# Serial_Board.net
KiCad netlist of a schematic drawn in EAGLE
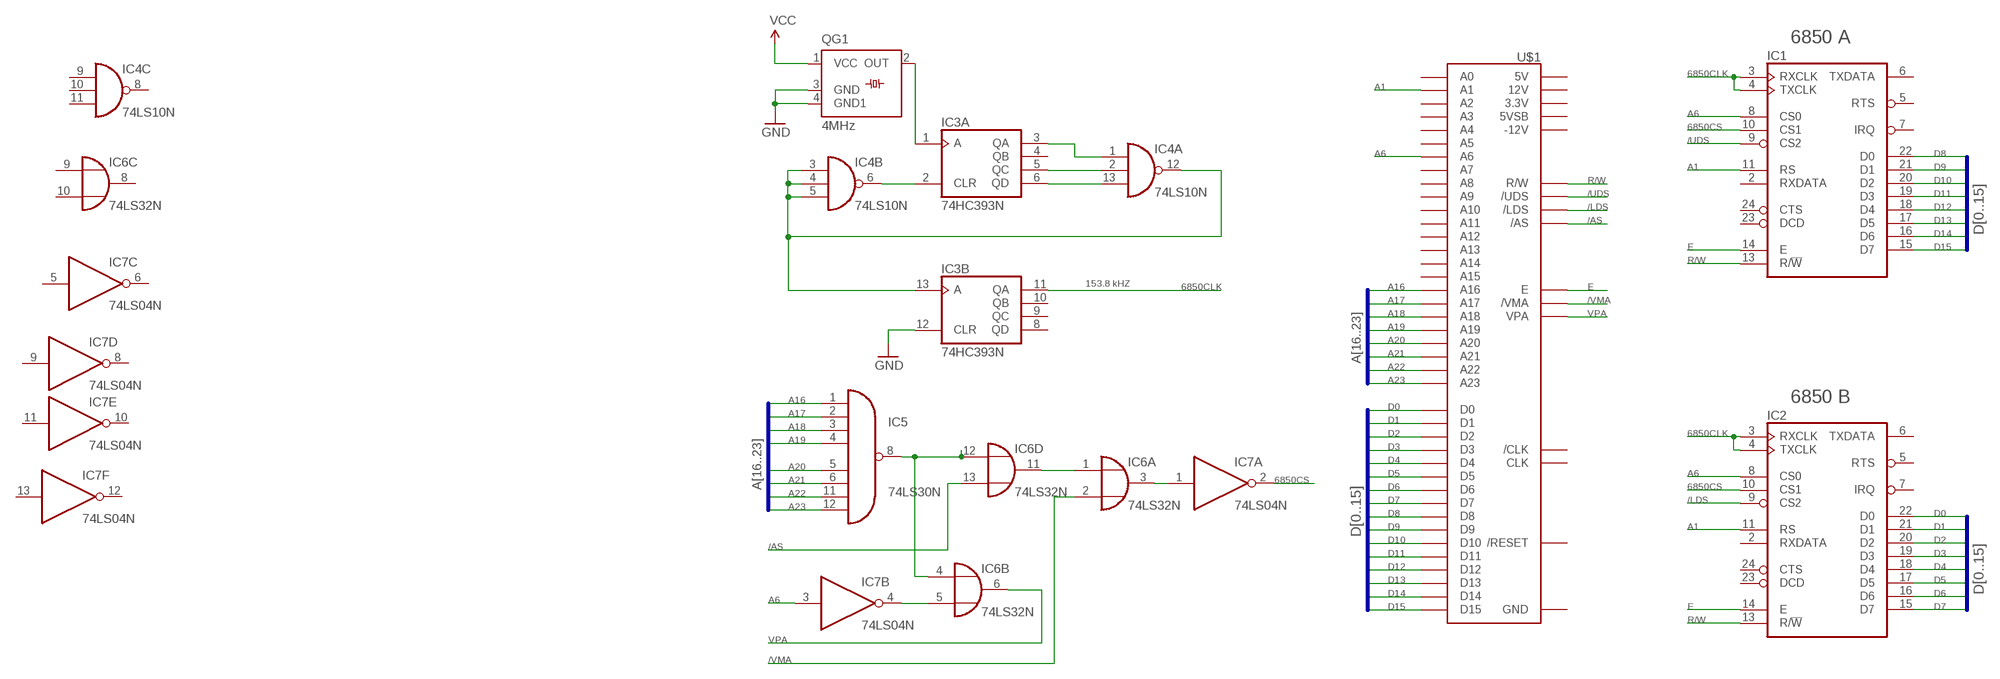
[diagram p0: schematic, sheet 1]

(export (version "E")
  (design (tool "Eeschema 10.0.6"))
  (components
    (comp (ref "IC1")
      (value "6850")
      (footprint "eagle-import:DIL24")
      (fields (field (name "MF") "NTE ELECTRONICS") (field (name "MPN") "NTE6850"))
      (libsource (lib "eagle-import") (part "6850"))
    )
    (comp (ref "IC2")
      (value "6850")
      (footprint "eagle-import:DIL24")
      (fields (field (name "MF") "NTE ELECTRONICS") (field (name "MPN") "NTE6850"))
      (libsource (lib "eagle-import") (part "6850"))
    )
    (comp (ref "IC3")
      (value "74HC393N")
      (footprint "eagle-import:DIL14")
      (libsource (lib "eagle-import") (part "74393NHC"))
    )
    (comp (ref "IC4")
      (value "74LS10N")
      (footprint "eagle-import:DIL14")
      (libsource (lib "eagle-import") (part "7410NLS"))
    )
    (comp (ref "IC5")
      (value "74LS30N")
      (footprint "eagle-import:DIL14")
      (libsource (lib "eagle-import") (part "7430NLS"))
    )
    (comp (ref "IC6")
      (value "74LS32N")
      (footprint "eagle-import:DIL14")
      (libsource (lib "eagle-import") (part "7432NLS"))
    )
    (comp (ref "IC7")
      (value "74LS04N")
      (footprint "eagle-import:DIL14")
      (libsource (lib "eagle-import") (part "7404NLS"))
    )
    (comp (ref "QG1")
      (value "4MHz")
      (footprint "eagle-import:TC49")
      (libsource (lib "eagle-import") (part "TC49C"))
    )
    (comp (ref "U$1")
      (value "BLANKBOARD")
      (footprint "eagle-import:BLANKBOARD")
      (libsource (lib "eagle-import") (part "BLANKBOARD"))
    )
  )
  (nets
    (net (code "1") (name "/6850CLK") (class "Default")
      (node (ref "IC1") (pin "3") (pinfunction "RXCLK_3") (pintype "input"))
      (node (ref "IC1") (pin "4") (pinfunction "TXCLK_4") (pintype "input"))
      (node (ref "IC2") (pin "3") (pinfunction "RXCLK_3") (pintype "input"))
      (node (ref "IC2") (pin "4") (pinfunction "TXCLK_4") (pintype "input"))
      (node (ref "IC3") (pin "11") (pinfunction "QA_11") (pintype "output"))
    )
    (net (code "2") (name "/6850CS") (class "Default")
      (node (ref "IC1") (pin "10") (pinfunction "CS1_10") (pintype "input"))
      (node (ref "IC2") (pin "10") (pinfunction "CS1_10") (pintype "input"))
      (node (ref "IC7") (pin "2") (pinfunction "O_2") (pintype "output"))
    )
    (net (code "3") (name "/A1") (class "Default")
      (node (ref "IC1") (pin "11") (pinfunction "RS_11") (pintype "input"))
      (node (ref "IC2") (pin "11") (pinfunction "RS_11") (pintype "input"))
      (node (ref "U$1") (pin "A1") (pinfunction "A1_A1") (pintype "bidirectional"))
    )
    (net (code "4") (name "/A6") (class "Default")
      (node (ref "IC1") (pin "8") (pinfunction "CS0_8") (pintype "input"))
      (node (ref "IC2") (pin "8") (pinfunction "CS0_8") (pintype "input"))
      (node (ref "IC7") (pin "3") (pinfunction "I_3") (pintype "input"))
      (node (ref "U$1") (pin "A6") (pinfunction "A6_A6") (pintype "bidirectional"))
    )
    (net (code "5") (name "/A16") (class "Default")
      (node (ref "IC5") (pin "1") (pinfunction "I0_1") (pintype "input"))
      (node (ref "U$1") (pin "A16") (pinfunction "A16_A16") (pintype "bidirectional"))
    )
    (net (code "6") (name "/A17") (class "Default")
      (node (ref "IC5") (pin "2") (pinfunction "I1_2") (pintype "input"))
      (node (ref "U$1") (pin "A17") (pinfunction "A17_A17") (pintype "bidirectional"))
    )
    (net (code "7") (name "/A18") (class "Default")
      (node (ref "IC5") (pin "3") (pinfunction "I2_3") (pintype "input"))
      (node (ref "U$1") (pin "A18") (pinfunction "A18_A18") (pintype "bidirectional"))
    )
    (net (code "8") (name "/A19") (class "Default")
      (node (ref "IC5") (pin "4") (pinfunction "I3_4") (pintype "input"))
      (node (ref "U$1") (pin "A19") (pinfunction "A19_A19") (pintype "bidirectional"))
    )
    (net (code "9") (name "/A20") (class "Default")
      (node (ref "IC5") (pin "5") (pinfunction "I4_5") (pintype "input"))
      (node (ref "U$1") (pin "A20") (pinfunction "A20_A20") (pintype "bidirectional"))
    )
    (net (code "10") (name "/A21") (class "Default")
      (node (ref "IC5") (pin "6") (pinfunction "I5_6") (pintype "input"))
      (node (ref "U$1") (pin "A21") (pinfunction "A21_A21") (pintype "bidirectional"))
    )
    (net (code "11") (name "/A22") (class "Default")
      (node (ref "IC5") (pin "11") (pinfunction "I6_11") (pintype "input"))
      (node (ref "U$1") (pin "A22") (pinfunction "A22_A22") (pintype "bidirectional"))
    )
    (net (code "12") (name "/A23") (class "Default")
      (node (ref "IC5") (pin "12") (pinfunction "I7_12") (pintype "input"))
      (node (ref "U$1") (pin "A23") (pinfunction "A23_A23") (pintype "bidirectional"))
    )
    (net (code "14") (name "/D0") (class "Default")
      (node (ref "IC2") (pin "22") (pinfunction "D0_22") (pintype "bidirectional"))
      (node (ref "U$1") (pin "D0") (pinfunction "D0_D0") (pintype "bidirectional"))
    )
    (net (code "15") (name "/D1") (class "Default")
      (node (ref "IC2") (pin "21") (pinfunction "D1_21") (pintype "bidirectional"))
      (node (ref "U$1") (pin "D1") (pinfunction "D1_D1") (pintype "bidirectional"))
    )
    (net (code "16") (name "/D2") (class "Default")
      (node (ref "IC2") (pin "20") (pinfunction "D2_20") (pintype "bidirectional"))
      (node (ref "U$1") (pin "D2") (pinfunction "D2_D2") (pintype "bidirectional"))
    )
    (net (code "17") (name "/D3") (class "Default")
      (node (ref "IC2") (pin "19") (pinfunction "D3_19") (pintype "bidirectional"))
      (node (ref "U$1") (pin "D3") (pinfunction "D3_D3") (pintype "bidirectional"))
    )
    (net (code "18") (name "/D4") (class "Default")
      (node (ref "IC2") (pin "18") (pinfunction "D4_18") (pintype "bidirectional"))
      (node (ref "U$1") (pin "D4") (pinfunction "D4_D4") (pintype "bidirectional"))
    )
    (net (code "19") (name "/D5") (class "Default")
      (node (ref "IC2") (pin "17") (pinfunction "D5_17") (pintype "bidirectional"))
      (node (ref "U$1") (pin "D5") (pinfunction "D5_D5") (pintype "bidirectional"))
    )
    (net (code "20") (name "/D6") (class "Default")
      (node (ref "IC2") (pin "16") (pinfunction "D6_16") (pintype "bidirectional"))
      (node (ref "U$1") (pin "D6") (pinfunction "D6_D6") (pintype "bidirectional"))
    )
    (net (code "21") (name "/D7") (class "Default")
      (node (ref "IC2") (pin "15") (pinfunction "D7_15") (pintype "bidirectional"))
      (node (ref "U$1") (pin "D7") (pinfunction "D7_D7") (pintype "bidirectional"))
    )
    (net (code "22") (name "/D8") (class "Default")
      (node (ref "IC1") (pin "22") (pinfunction "D0_22") (pintype "bidirectional"))
      (node (ref "U$1") (pin "D8") (pinfunction "D8_D8") (pintype "bidirectional"))
    )
    (net (code "23") (name "/D9") (class "Default")
      (node (ref "IC1") (pin "21") (pinfunction "D1_21") (pintype "bidirectional"))
      (node (ref "U$1") (pin "D9") (pinfunction "D9_D9") (pintype "bidirectional"))
    )
    (net (code "24") (name "/D10") (class "Default")
      (node (ref "IC1") (pin "20") (pinfunction "D2_20") (pintype "bidirectional"))
      (node (ref "U$1") (pin "D10") (pinfunction "D10_D10") (pintype "bidirectional"))
    )
    (net (code "25") (name "/D11") (class "Default")
      (node (ref "IC1") (pin "19") (pinfunction "D3_19") (pintype "bidirectional"))
      (node (ref "U$1") (pin "D11") (pinfunction "D11_D11") (pintype "bidirectional"))
    )
    (net (code "26") (name "/D12") (class "Default")
      (node (ref "IC1") (pin "18") (pinfunction "D4_18") (pintype "bidirectional"))
      (node (ref "U$1") (pin "D12") (pinfunction "D12_D12") (pintype "bidirectional"))
    )
    (net (code "27") (name "/D13") (class "Default")
      (node (ref "IC1") (pin "17") (pinfunction "D5_17") (pintype "bidirectional"))
      (node (ref "U$1") (pin "D13") (pinfunction "D13_D13") (pintype "bidirectional"))
    )
    (net (code "28") (name "/D14") (class "Default")
      (node (ref "IC1") (pin "16") (pinfunction "D6_16") (pintype "bidirectional"))
      (node (ref "U$1") (pin "D14") (pinfunction "D14_D14") (pintype "bidirectional"))
    )
    (net (code "29") (name "/D15") (class "Default")
      (node (ref "IC1") (pin "15") (pinfunction "D7_15") (pintype "bidirectional"))
      (node (ref "U$1") (pin "D15") (pinfunction "D15_D15") (pintype "bidirectional"))
    )
    (net (code "31") (name "/E") (class "Default")
      (node (ref "IC1") (pin "14") (pinfunction "E_14") (pintype "input"))
      (node (ref "IC2") (pin "14") (pinfunction "E_14") (pintype "input"))
      (node (ref "U$1") (pin "E") (pinfunction "E_E") (pintype "bidirectional"))
    )
    (net (code "32") (name "/R{slash}W") (class "Default")
      (node (ref "IC1") (pin "13") (pinfunction "R/~{W}_13") (pintype "input"))
      (node (ref "IC2") (pin "13") (pinfunction "R/~{W}_13") (pintype "input"))
      (node (ref "U$1") (pin "R/W") (pinfunction "R/W_R/W") (pintype "bidirectional"))
    )
    (net (code "33") (name "/VPA") (class "Default")
      (node (ref "IC6") (pin "6") (pinfunction "O_6") (pintype "output"))
      (node (ref "U$1") (pin "VPA") (pinfunction "VPA_VPA") (pintype "bidirectional"))
    )
    (net (code "34") (name "/{slash}AS") (class "Default")
      (node (ref "IC6") (pin "13") (pinfunction "I1_13") (pintype "input"))
      (node (ref "U$1") (pin "/AS") (pinfunction "/AS_/AS") (pintype "bidirectional"))
    )
    (net (code "35") (name "/{slash}LDS") (class "Default")
      (node (ref "IC2") (pin "9") (pinfunction "CS2_9") (pintype "input"))
      (node (ref "U$1") (pin "/LDS") (pinfunction "/LDS_/LDS") (pintype "bidirectional"))
    )
    (net (code "36") (name "/{slash}UDS") (class "Default")
      (node (ref "IC1") (pin "9") (pinfunction "CS2_9") (pintype "input"))
      (node (ref "U$1") (pin "/UDS") (pinfunction "/UDS_/UDS") (pintype "bidirectional"))
    )
    (net (code "37") (name "/{slash}VMA") (class "Default")
      (node (ref "IC6") (pin "2") (pinfunction "I1_2") (pintype "input"))
      (node (ref "U$1") (pin "/VMA") (pinfunction "/VMA_/VMA") (pintype "bidirectional"))
    )
    (net (code "38") (name "GND") (class "Default")
      (node (ref "IC3") (pin "12") (pinfunction "CLR_12") (pintype "input"))
      (node (ref "QG1") (pin "3") (pinfunction "GND_3") (pintype "power_in"))
      (node (ref "QG1") (pin "4") (pinfunction "GND1_4") (pintype "power_in"))
    )
    (net (code "39") (name "Net-(IC3A-A)") (class "Default")
      (node (ref "IC3") (pin "1") (pinfunction "A_1") (pintype "input"))
      (node (ref "QG1") (pin "2") (pinfunction "OUT_2") (pintype "output"))
    )
    (net (code "40") (name "Net-(IC3A-CLR)") (class "Default")
      (node (ref "IC3") (pin "2") (pinfunction "CLR_2") (pintype "input"))
      (node (ref "IC4") (pin "6") (pinfunction "O_6") (pintype "output"))
    )
    (net (code "41") (name "Net-(IC3A-QA)") (class "Default")
      (node (ref "IC3") (pin "3") (pinfunction "QA_3") (pintype "output"))
      (node (ref "IC4") (pin "1") (pinfunction "I0_1") (pintype "input"))
    )
    (net (code "42") (name "Net-(IC3A-QC)") (class "Default")
      (node (ref "IC3") (pin "5") (pinfunction "QC_5") (pintype "output"))
      (node (ref "IC4") (pin "2") (pinfunction "I1_2") (pintype "input"))
    )
    (net (code "43") (name "Net-(IC3A-QD)") (class "Default")
      (node (ref "IC3") (pin "6") (pinfunction "QD_6") (pintype "output"))
      (node (ref "IC4") (pin "13") (pinfunction "I2_13") (pintype "input"))
    )
    (net (code "44") (name "Net-(IC3B-A)") (class "Default")
      (node (ref "IC3") (pin "13") (pinfunction "A_13") (pintype "input"))
      (node (ref "IC4") (pin "12") (pinfunction "O_12") (pintype "output"))
      (node (ref "IC4") (pin "3") (pinfunction "I0_3") (pintype "input"))
      (node (ref "IC4") (pin "4") (pinfunction "I1_4") (pintype "input"))
      (node (ref "IC4") (pin "5") (pinfunction "I2_5") (pintype "input"))
    )
    (net (code "45") (name "Net-(IC5A-O)") (class "Default")
      (node (ref "IC5") (pin "8") (pinfunction "O_8") (pintype "output"))
      (node (ref "IC6") (pin "12") (pinfunction "I0_12") (pintype "input"))
      (node (ref "IC6") (pin "4") (pinfunction "I0_4") (pintype "input"))
    )
    (net (code "46") (name "Net-(IC6A-I0)") (class "Default")
      (node (ref "IC6") (pin "1") (pinfunction "I0_1") (pintype "input"))
      (node (ref "IC6") (pin "11") (pinfunction "O_11") (pintype "output"))
    )
    (net (code "47") (name "Net-(IC6A-O)") (class "Default")
      (node (ref "IC6") (pin "3") (pinfunction "O_3") (pintype "output"))
      (node (ref "IC7") (pin "1") (pinfunction "I_1") (pintype "input"))
    )
    (net (code "48") (name "Net-(IC6B-I1)") (class "Default")
      (node (ref "IC6") (pin "5") (pinfunction "I1_5") (pintype "input"))
      (node (ref "IC7") (pin "4") (pinfunction "O_4") (pintype "output"))
    )
    (net (code "49") (name "VCC") (class "Default")
      (node (ref "QG1") (pin "1") (pinfunction "VCC_1") (pintype "power_in"))
    )
    (net (code "50") (name "unconnected-(IC1A-CTS-Pad24)") (class "Default")
      (node (ref "IC1") (pin "24") (pinfunction "CTS_24") (pintype "input"))
    )
    (net (code "51") (name "unconnected-(IC1A-DCD-Pad23)") (class "Default")
      (node (ref "IC1") (pin "23") (pinfunction "DCD_23") (pintype "input"))
    )
    (net (code "52") (name "unconnected-(IC1A-IRQ-Pad7)") (class "Default")
      (node (ref "IC1") (pin "7") (pinfunction "IRQ_7") (pintype "output"))
    )
    (net (code "53") (name "unconnected-(IC1A-RTS-Pad5)") (class "Default")
      (node (ref "IC1") (pin "5") (pinfunction "RTS_5") (pintype "output"))
    )
    (net (code "54") (name "unconnected-(IC1A-RXDATA-Pad2)") (class "Default")
      (node (ref "IC1") (pin "2") (pinfunction "RXDATA_2") (pintype "input"))
    )
    (net (code "55") (name "unconnected-(IC1A-TXDATA-Pad6)") (class "Default")
      (node (ref "IC1") (pin "6") (pinfunction "TXDATA_6") (pintype "output"))
    )
    (net (code "56") (name "unconnected-(IC2A-CTS-Pad24)") (class "Default")
      (node (ref "IC2") (pin "24") (pinfunction "CTS_24") (pintype "input"))
    )
    (net (code "57") (name "unconnected-(IC2A-DCD-Pad23)") (class "Default")
      (node (ref "IC2") (pin "23") (pinfunction "DCD_23") (pintype "input"))
    )
    (net (code "58") (name "unconnected-(IC2A-IRQ-Pad7)") (class "Default")
      (node (ref "IC2") (pin "7") (pinfunction "IRQ_7") (pintype "output"))
    )
    (net (code "59") (name "unconnected-(IC2A-RTS-Pad5)") (class "Default")
      (node (ref "IC2") (pin "5") (pinfunction "RTS_5") (pintype "output"))
    )
    (net (code "60") (name "unconnected-(IC2A-RXDATA-Pad2)") (class "Default")
      (node (ref "IC2") (pin "2") (pinfunction "RXDATA_2") (pintype "input"))
    )
    (net (code "61") (name "unconnected-(IC2A-TXDATA-Pad6)") (class "Default")
      (node (ref "IC2") (pin "6") (pinfunction "TXDATA_6") (pintype "output"))
    )
    (net (code "62") (name "unconnected-(IC3A-QB-Pad4)") (class "Default")
      (node (ref "IC3") (pin "4") (pinfunction "QB_4") (pintype "output"))
    )
    (net (code "63") (name "unconnected-(IC3B-QB-Pad10)") (class "Default")
      (node (ref "IC3") (pin "10") (pinfunction "QB_10") (pintype "output"))
    )
    (net (code "64") (name "unconnected-(IC3B-QC-Pad9)") (class "Default")
      (node (ref "IC3") (pin "9") (pinfunction "QC_9") (pintype "output"))
    )
    (net (code "65") (name "unconnected-(IC3B-QD-Pad8)") (class "Default")
      (node (ref "IC3") (pin "8") (pinfunction "QD_8") (pintype "output"))
    )
    (net (code "66") (name "unconnected-(IC4C-I0-Pad9)") (class "Default")
      (node (ref "IC4") (pin "9") (pinfunction "I0_9") (pintype "input"))
    )
    (net (code "67") (name "unconnected-(IC4C-I1-Pad10)") (class "Default")
      (node (ref "IC4") (pin "10") (pinfunction "I1_10") (pintype "input"))
    )
    (net (code "68") (name "unconnected-(IC4C-I2-Pad11)") (class "Default")
      (node (ref "IC4") (pin "11") (pinfunction "I2_11") (pintype "input"))
    )
    (net (code "69") (name "unconnected-(IC4C-O-Pad8)") (class "Default")
      (node (ref "IC4") (pin "8") (pinfunction "O_8") (pintype "output"))
    )
    (net (code "70") (name "unconnected-(IC6C-I0-Pad9)") (class "Default")
      (node (ref "IC6") (pin "9") (pinfunction "I0_9") (pintype "input"))
    )
    (net (code "71") (name "unconnected-(IC6C-I1-Pad10)") (class "Default")
      (node (ref "IC6") (pin "10") (pinfunction "I1_10") (pintype "input"))
    )
    (net (code "72") (name "unconnected-(IC6C-O-Pad8)") (class "Default")
      (node (ref "IC6") (pin "8") (pinfunction "O_8") (pintype "output"))
    )
    (net (code "73") (name "unconnected-(IC7C-I-Pad5)") (class "Default")
      (node (ref "IC7") (pin "5") (pinfunction "I_5") (pintype "input"))
    )
    (net (code "74") (name "unconnected-(IC7C-O-Pad6)") (class "Default")
      (node (ref "IC7") (pin "6") (pinfunction "O_6") (pintype "output"))
    )
    (net (code "75") (name "unconnected-(IC7D-I-Pad9)") (class "Default")
      (node (ref "IC7") (pin "9") (pinfunction "I_9") (pintype "input"))
    )
    (net (code "76") (name "unconnected-(IC7D-O-Pad8)") (class "Default")
      (node (ref "IC7") (pin "8") (pinfunction "O_8") (pintype "output"))
    )
    (net (code "77") (name "unconnected-(IC7E-I-Pad11)") (class "Default")
      (node (ref "IC7") (pin "11") (pinfunction "I_11") (pintype "input"))
    )
    (net (code "78") (name "unconnected-(IC7E-O-Pad10)") (class "Default")
      (node (ref "IC7") (pin "10") (pinfunction "O_10") (pintype "output"))
    )
    (net (code "79") (name "unconnected-(IC7F-I-Pad13)") (class "Default")
      (node (ref "IC7") (pin "13") (pinfunction "I_13") (pintype "input"))
    )
    (net (code "80") (name "unconnected-(IC7F-O-Pad12)") (class "Default")
      (node (ref "IC7") (pin "12") (pinfunction "O_12") (pintype "output"))
    )
    (net (code "81") (name "unconnected-(U$1-3.3V-Pad3V3)") (class "Default")
      (node (ref "U$1") (pin "3V3") (pinfunction "3.3V_3V3") (pintype "bidirectional"))
    )
    (net (code "82") (name "unconnected-(U$1-Pad-12V)") (class "Default")
      (node (ref "U$1") (pin "-12V") (pinfunction "-12V_-12V") (pintype "bidirectional"))
    )
    (net (code "83") (name "unconnected-(U$1-Pad5V)") (class "Default")
      (node (ref "U$1") (pin "5V") (pinfunction "5V_5V") (pintype "bidirectional"))
    )
    (net (code "84") (name "unconnected-(U$1-Pad5VSB)") (class "Default")
      (node (ref "U$1") (pin "5VSB") (pinfunction "5VSB_5VSB") (pintype "bidirectional"))
    )
    (net (code "85") (name "unconnected-(U$1-Pad12V)") (class "Default")
      (node (ref "U$1") (pin "12V") (pinfunction "12V_12V") (pintype "bidirectional"))
    )
    (net (code "86") (name "unconnected-(U$1-PadA0)") (class "Default")
      (node (ref "U$1") (pin "A0") (pinfunction "A0_A0") (pintype "bidirectional"))
    )
    (net (code "87") (name "unconnected-(U$1-PadA2)") (class "Default")
      (node (ref "U$1") (pin "A2") (pinfunction "A2_A2") (pintype "bidirectional"))
    )
    (net (code "88") (name "unconnected-(U$1-PadA3)") (class "Default")
      (node (ref "U$1") (pin "A3") (pinfunction "A3_A3") (pintype "bidirectional"))
    )
    (net (code "89") (name "unconnected-(U$1-PadA4)") (class "Default")
      (node (ref "U$1") (pin "A4") (pinfunction "A4_A4") (pintype "bidirectional"))
    )
    (net (code "90") (name "unconnected-(U$1-PadA5)") (class "Default")
      (node (ref "U$1") (pin "A5") (pinfunction "A5_A5") (pintype "bidirectional"))
    )
    (net (code "91") (name "unconnected-(U$1-PadA7)") (class "Default")
      (node (ref "U$1") (pin "A7") (pinfunction "A7_A7") (pintype "bidirectional"))
    )
    (net (code "92") (name "unconnected-(U$1-PadA8)") (class "Default")
      (node (ref "U$1") (pin "A8") (pinfunction "A8_A8") (pintype "bidirectional"))
    )
    (net (code "93") (name "unconnected-(U$1-PadA9)") (class "Default")
      (node (ref "U$1") (pin "A9") (pinfunction "A9_A9") (pintype "bidirectional"))
    )
    (net (code "94") (name "unconnected-(U$1-PadA10)") (class "Default")
      (node (ref "U$1") (pin "A10") (pinfunction "A10_A10") (pintype "bidirectional"))
    )
    (net (code "95") (name "unconnected-(U$1-PadA11)") (class "Default")
      (node (ref "U$1") (pin "A11") (pinfunction "A11_A11") (pintype "bidirectional"))
    )
    (net (code "96") (name "unconnected-(U$1-PadA12)") (class "Default")
      (node (ref "U$1") (pin "A12") (pinfunction "A12_A12") (pintype "bidirectional"))
    )
    (net (code "97") (name "unconnected-(U$1-PadA13)") (class "Default")
      (node (ref "U$1") (pin "A13") (pinfunction "A13_A13") (pintype "bidirectional"))
    )
    (net (code "98") (name "unconnected-(U$1-PadA14)") (class "Default")
      (node (ref "U$1") (pin "A14") (pinfunction "A14_A14") (pintype "bidirectional"))
    )
    (net (code "99") (name "unconnected-(U$1-PadA15)") (class "Default")
      (node (ref "U$1") (pin "A15") (pinfunction "A15_A15") (pintype "bidirectional"))
    )
    (net (code "100") (name "unconnected-(U$1-PadCLK)") (class "Default")
      (node (ref "U$1") (pin "CLK") (pinfunction "CLK_CLK") (pintype "bidirectional"))
    )
    (net (code "101") (name "unconnected-(U$1-PadGND)") (class "Default")
      (node (ref "U$1") (pin "GND") (pinfunction "GND_GND") (pintype "bidirectional"))
    )
    (net (code "102") (name "unconnected-(U$1-Pad{slash}CLK)") (class "Default")
      (node (ref "U$1") (pin "/CLK") (pinfunction "/CLK_/CLK") (pintype "bidirectional"))
    )
    (net (code "103") (name "unconnected-(U$1-Pad{slash}RESET)") (class "Default")
      (node (ref "U$1") (pin "/RESET") (pinfunction "/RESET_/RESET") (pintype "bidirectional"))
    )
  )
)
